# miniboard_1.net
KiCad netlist of a schematic drawn in EAGLE
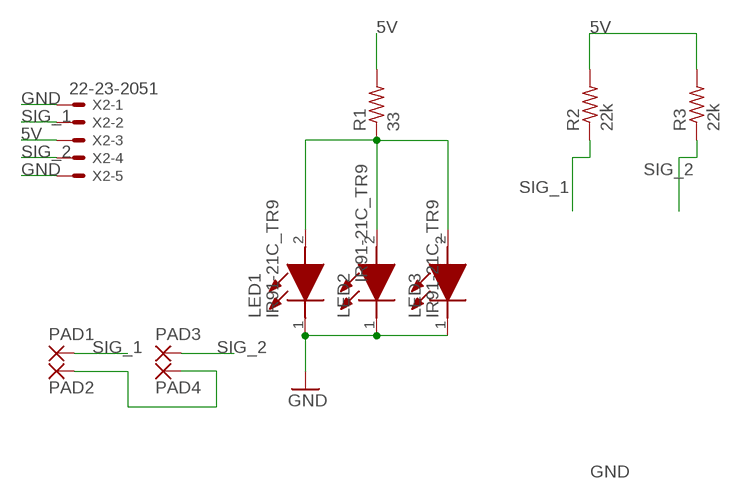
[diagram p0: schematic, sheet 1]

(export (version "E")
  (design (tool "Eeschema 10.0.6"))
  (components
    (comp (ref "LED1")
      (value "IR91-21C_TR9")
      (footprint "eagle-import:SODFL7422X280N")
      (fields (field (name "MANUFACTURER_PART_NUMBER") "IR91-21C/TR9"))
      (libsource (lib "eagle-import") (part "IR91-21C_TR9"))
    )
    (comp (ref "LED2")
      (value "IR91-21C_TR9")
      (footprint "eagle-import:SODFL7422X280N")
      (fields (field (name "MANUFACTURER_PART_NUMBER") "IR91-21C/TR9"))
      (libsource (lib "eagle-import") (part "IR91-21C_TR9"))
    )
    (comp (ref "LED3")
      (value "IR91-21C_TR9")
      (footprint "eagle-import:SODFL7422X280N")
      (fields (field (name "MANUFACTURER_PART_NUMBER") "IR91-21C/TR9"))
      (libsource (lib "eagle-import") (part "IR91-21C_TR9"))
    )
    (comp (ref "PAD1")
      (value "SMD2")
      (footprint "eagle-import:SMD1,27-2,54")
      (libsource (lib "eagle-import") (part "SMD2"))
    )
    (comp (ref "PAD2")
      (value "SMD2")
      (footprint "eagle-import:SMD1,27-2,54")
      (libsource (lib "eagle-import") (part "SMD2"))
    )
    (comp (ref "PAD3")
      (value "SMD2")
      (footprint "eagle-import:SMD1,27-2,54")
      (libsource (lib "eagle-import") (part "SMD2"))
    )
    (comp (ref "PAD4")
      (value "SMD2")
      (footprint "eagle-import:SMD1,27-2,54")
      (libsource (lib "eagle-import") (part "SMD2"))
    )
    (comp (ref "R1")
      (value "33")
      (footprint "eagle-import:0204_5")
      (libsource (lib "eagle-import") (part "R-US_0204/5"))
    )
    (comp (ref "R2")
      (value "22k")
      (footprint "eagle-import:0204_5")
      (libsource (lib "eagle-import") (part "R-US_0204/5"))
    )
    (comp (ref "R3")
      (value "22k")
      (footprint "eagle-import:0204_5")
      (libsource (lib "eagle-import") (part "R-US_0204/5"))
    )
    (comp (ref "X2")
      (value "22-23-2051")
      (footprint "eagle-import:22-23-2051")
      (fields (field (name "MF") "MOLEX"))
      (libsource (lib "eagle-import") (part "22-23-2051"))
    )
  )
  (nets
    (net (code "1") (name "/5V") (class "Default")
      (node (ref "R1") (pin "2") (pinfunction "2_2") (pintype "passive"))
      (node (ref "R2") (pin "2") (pinfunction "2_2") (pintype "passive"))
      (node (ref "R3") (pin "2") (pinfunction "2_2") (pintype "passive"))
      (node (ref "X2") (pin "3") (pinfunction "S_3") (pintype "passive"))
    )
    (net (code "2") (name "/SIG_1") (class "Default")
      (node (ref "PAD1") (pin "1") (pinfunction "P_1") (pintype "passive"))
      (node (ref "R2") (pin "1") (pinfunction "1_1") (pintype "passive"))
      (node (ref "X2") (pin "2") (pinfunction "S_2") (pintype "passive"))
    )
    (net (code "3") (name "/SIG_2") (class "Default")
      (node (ref "PAD3") (pin "1") (pinfunction "P_1") (pintype "passive"))
      (node (ref "R3") (pin "1") (pinfunction "1_1") (pintype "passive"))
      (node (ref "X2") (pin "4") (pinfunction "S_4") (pintype "passive"))
    )
    (net (code "4") (name "GND") (class "Default")
      (node (ref "LED1") (pin "1") (pinfunction "K_1") (pintype "output"))
      (node (ref "LED2") (pin "1") (pinfunction "K_1") (pintype "output"))
      (node (ref "LED3") (pin "1") (pinfunction "K_1") (pintype "output"))
      (node (ref "PAD2") (pin "1") (pinfunction "P_1") (pintype "passive"))
      (node (ref "PAD4") (pin "1") (pinfunction "P_1") (pintype "passive"))
      (node (ref "X2") (pin "1") (pinfunction "S_1") (pintype "passive"))
      (node (ref "X2") (pin "5") (pinfunction "S_5") (pintype "passive"))
    )
    (net (code "5") (name "Net-(LED1-A)") (class "Default")
      (node (ref "LED1") (pin "2") (pinfunction "A_2") (pintype "input"))
      (node (ref "LED2") (pin "2") (pinfunction "A_2") (pintype "input"))
      (node (ref "LED3") (pin "2") (pinfunction "A_2") (pintype "input"))
      (node (ref "R1") (pin "1") (pinfunction "1_1") (pintype "passive"))
    )
  )
)
